# USB_HUB_SUPPORT.net
KiCad netlist of a schematic drawn in Altium Designer
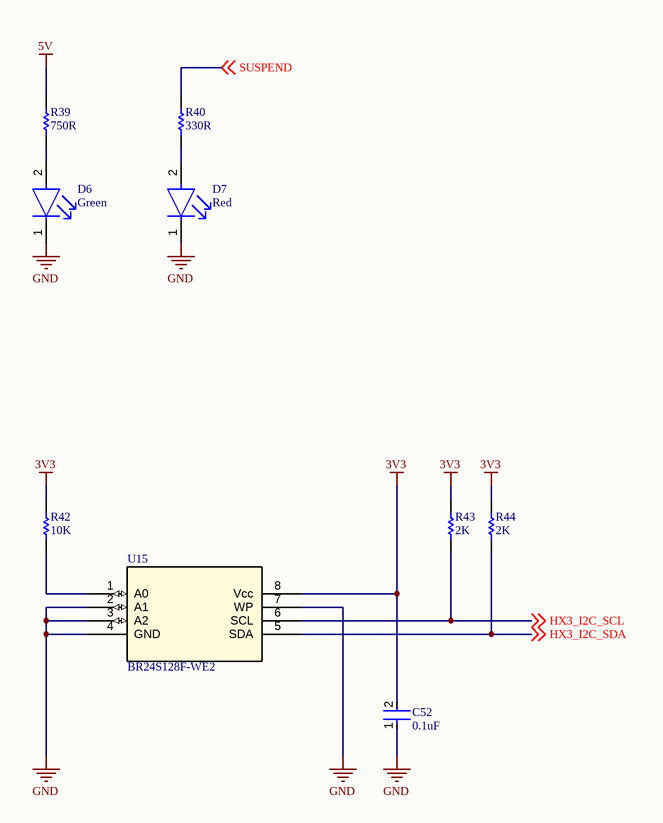
[diagram p0: USB_HUB_SUPPORT.SchDoc]

(export (version "E")
  (design (tool "Eeschema 10.0.6"))
  (components
    (comp (ref "C52")
      (value "0.1uF")
      (footprint "FP-CC0201-BA-MFG")
      (description "CAP CER 0.1UF 6.3V X5R 0201")
      (fields (field (name "MANUFACTURER") "Yageo") (field (name "TOLERANCE") "0.1"))
      (libsource (lib "Altium Content Vault") (part "11868f565c42a9108669ba33697ecf6"))
    )
    (comp (ref "D6")
      (value "Green")
      (footprint "FP-LTST-C190KGKT-MFG")
      (description "LED GREEN CLEAR CHIP SMD")
      (libsource (lib "Altium Content Vault") (part "8706943c75ba83719d021d2fdc84c58"))
    )
    (comp (ref "D7")
      (value "Red")
      (footprint "FP-LTST-C190KRKT-MFG")
      (description "LED RED CLEAR CHIP SMD")
      (libsource (lib "Altium Content Vault") (part "8706943c75ba83719d021d2fdc84c58"))
    )
    (comp (ref "R39")
      (value "750R")
      (footprint "RESC1005X40X25ML05T05")
      (fields (field (name "PART NUMBER") "ERJ-2RKF7500X") (field (name "MANUFACTURER") "Panasonic"))
      (libsource (lib "Altium Content Vault") (part "RES"))
    )
    (comp (ref "R40")
      (value "330R")
      (footprint "RESC1005X40X25ML05T05")
      (fields (field (name "MANUFACTURER") "Panasonic") (field (name "PART NUMBER") "ERJ2RKF3300X"))
      (libsource (lib "Altium Content Vault") (part "RES"))
    )
    (comp (ref "R42")
      (value "10K")
      (footprint "RESC1005X40X25ML05T10")
      (fields (field (name "PART NUMBER") "CRCW040210K0FKEDHP") (field (name "MANUFACTURER") "Vishay Dale"))
      (libsource (lib "Altium Content Vault") (part "RES"))
    )
    (comp (ref "R43")
      (value "2K")
      (footprint "RESC1005X40X20LL05T10")
      (fields (field (name "PART NUMBER") "TNPW04022K00BEED") (field (name "MANUFACTURER") "Vishay Dale"))
      (libsource (lib "Altium Content Vault") (part "RES"))
    )
    (comp (ref "R44")
      (value "2K")
      (footprint "RESC1005X40X20LL05T10")
      (fields (field (name "PART NUMBER") "TNPW04022K00BEED") (field (name "MANUFACTURER") "Vishay Dale"))
      (libsource (lib "Altium Content Vault") (part "RES"))
    )
    (comp (ref "U15")
      (value "BR24S128F-WE2")
      (footprint "SOP8_ROM")
      (description "No Description Available")
      (fields (field (name "COPYRIGHT") "Copyright (C) 2022 Ultra Librarian. All rights reserved."))
      (libsource (lib "BR24S128F-WE2") (part "BR24S128F-WE2"))
    )
  )
  (nets
    (net (code "1") (name "3V3") (class "Default")
      (node (ref "C52") (pin "2") (pinfunction "2_2") (pintype "passive"))
      (node (ref "R42") (pin "2") (pinfunction "2_2") (pintype "passive"))
      (node (ref "R43") (pin "2") (pinfunction "2_2") (pintype "passive"))
      (node (ref "R44") (pin "2") (pinfunction "2_2") (pintype "passive"))
      (node (ref "U15") (pin "8") (pinfunction "Vcc_8") (pintype "power_in"))
    )
    (net (code "2") (name "5V") (class "Default")
      (node (ref "R39") (pin "2") (pinfunction "2_2") (pintype "passive"))
    )
    (net (code "3") (name "GND") (class "Default")
      (node (ref "C52") (pin "1") (pinfunction "1_1") (pintype "passive"))
      (node (ref "D6") (pin "1") (pinfunction "C_1") (pintype "passive"))
      (node (ref "D7") (pin "1") (pinfunction "C_1") (pintype "passive"))
      (node (ref "U15") (pin "2") (pinfunction "A1_2") (pintype "bidirectional"))
      (node (ref "U15") (pin "3") (pinfunction "A2_3") (pintype "bidirectional"))
      (node (ref "U15") (pin "4") (pinfunction "GND_4") (pintype "passive"))
      (node (ref "U15") (pin "7") (pinfunction "WP_7") (pintype "passive"))
    )
    (net (code "4") (name "HX3_I2C_SCL") (class "Default")
      (node (ref "R43") (pin "1") (pinfunction "1_1") (pintype "passive"))
      (node (ref "U15") (pin "6") (pinfunction "SCL_6") (pintype "passive"))
    )
    (net (code "5") (name "HX3_I2C_SDA") (class "Default")
      (node (ref "R44") (pin "1") (pinfunction "1_1") (pintype "passive"))
      (node (ref "U15") (pin "5") (pinfunction "SDA_5") (pintype "passive"))
    )
    (net (code "6") (name "Net-(D6-A)") (class "Default")
      (node (ref "D6") (pin "2") (pinfunction "A_2") (pintype "passive"))
      (node (ref "R39") (pin "1") (pinfunction "1_1") (pintype "passive"))
    )
    (net (code "7") (name "Net-(D7-A)") (class "Default")
      (node (ref "D7") (pin "2") (pinfunction "A_2") (pintype "passive"))
      (node (ref "R40") (pin "1") (pinfunction "1_1") (pintype "passive"))
    )
    (net (code "8") (name "Net-(U15-A0)") (class "Default")
      (node (ref "R42") (pin "1") (pinfunction "1_1") (pintype "passive"))
      (node (ref "U15") (pin "1") (pinfunction "A0_1") (pintype "bidirectional"))
    )
    (net (code "9") (name "SUSPEND") (class "Default")
      (node (ref "R40") (pin "2") (pinfunction "2_2") (pintype "passive"))
    )
  )
)
